# Power.net
KiCad netlist of a schematic drawn in Altium Designer
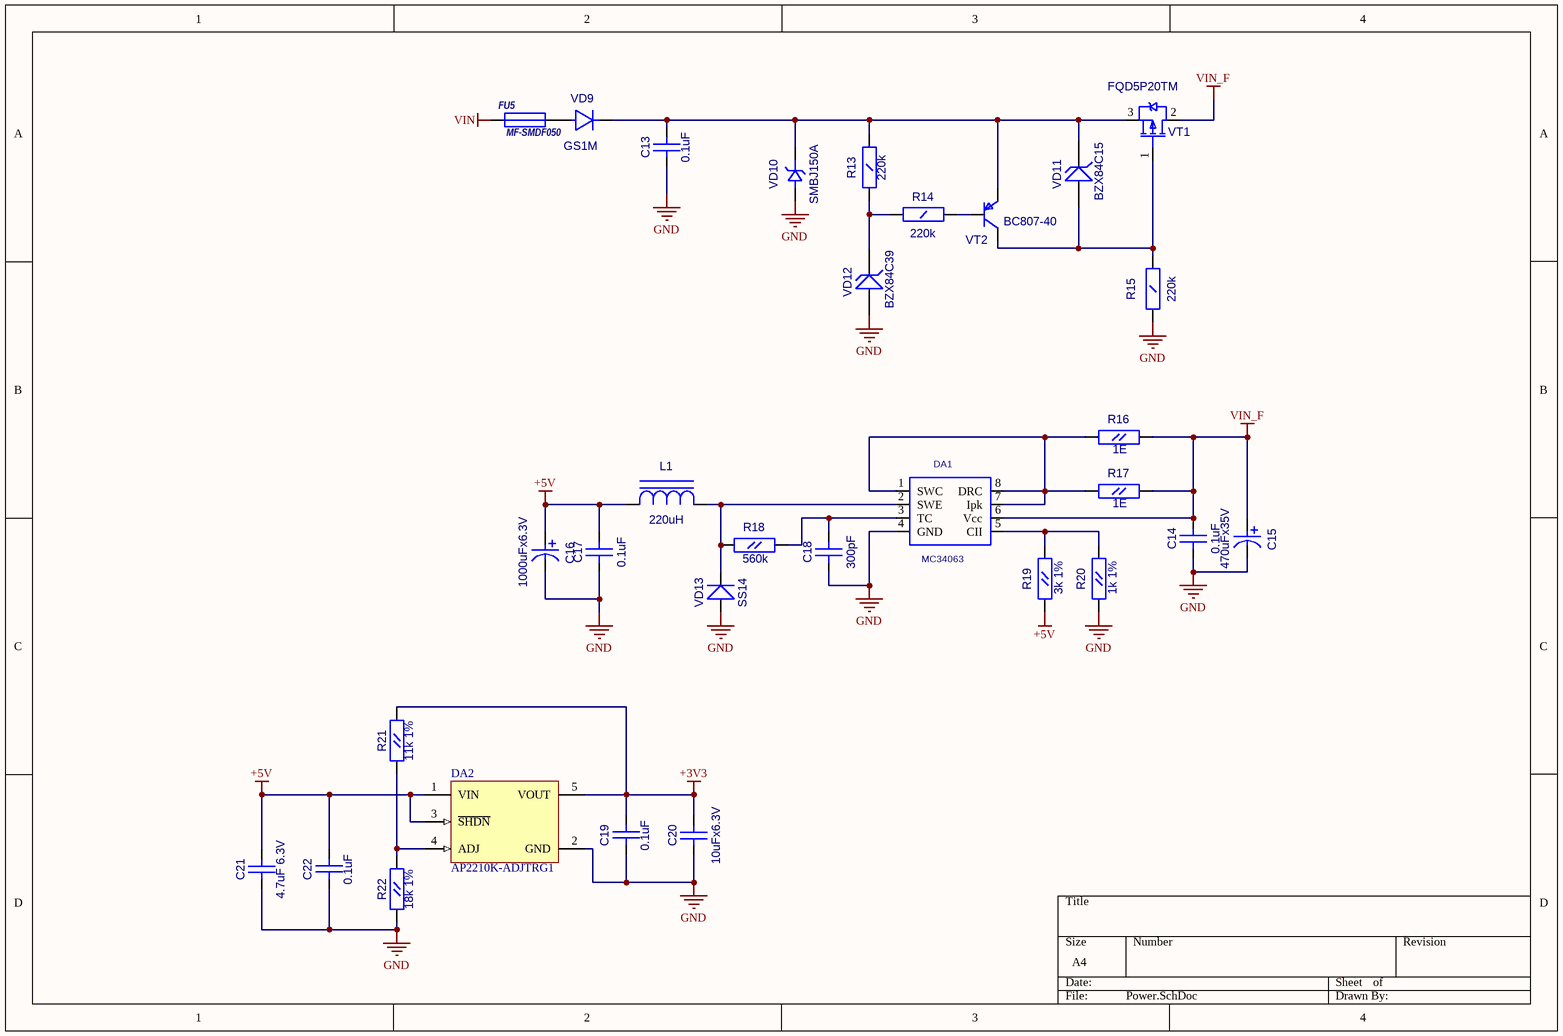
[diagram p0: Power.SchDoc]

(export (version "E")
  (design (tool "Eeschema 10.0.6"))
  (components
    (comp (ref "C13")
      (value "0.1uF")
      (footprint "CC1206")
      (description "CC1206")
      (libsource (lib "gprs_modem_2") (part "CC1206"))
    )
    (comp (ref "C14")
      (value "0.1uF")
      (footprint "CC0603")
      (description "CC0603")
      (libsource (lib "gprs_modem_2") (part "CC0603"))
    )
    (comp (ref "C15")
      (value "470uFx35V")
      (footprint "CC16X10_CAP0.5(1)(Primary)")
      (description "CAP0.5(1)")
      (libsource (lib "gprs_modem_2") (part "CAP0.5(1)"))
    )
    (comp (ref "C16")
      (value "1000uFx6.3V")
      (footprint "CC8X3.5")
      (description "CAP0.35")
      (libsource (lib "gprs_modem_2") (part "CAP0.35"))
    )
    (comp (ref "C17")
      (value "0.1uF")
      (footprint "CC0603")
      (description "CC0603")
      (libsource (lib "gprs_modem_2") (part "CC0603"))
    )
    (comp (ref "C18")
      (value "300pF")
      (footprint "CC0603")
      (description "CC0603")
      (libsource (lib "gprs_modem_2") (part "CC0603"))
    )
    (comp (ref "C19")
      (value "0.1uF")
      (footprint "CC0603")
      (description "CC0603")
      (libsource (lib "gprs_modem_2") (part "CC0603"))
    )
    (comp (ref "C20")
      (value "10uFx6.3V")
      (footprint "CC0805")
      (description "CC0805")
      (libsource (lib "gprs_modem_2") (part "CC0805"))
    )
    (comp (ref "C21")
      (value "4.7uF 6.3V")
      (footprint "CC0805")
      (description "CC0805")
      (libsource (lib "gprs_modem_2") (part "CC0805"))
    )
    (comp (ref "C22")
      (value "0.1uF")
      (footprint "CC0603")
      (description "CC0603")
      (libsource (lib "gprs_modem_2") (part "CC0603"))
    )
    (comp (ref "DA1") (value "MC34063") (footprint "SO-8") (libsource (lib "Schetchik") (part "MC34063")))
    (comp (ref "DA2")
      (value "AP2210K-ADJTRG1")
      (footprint "SOT23-5")
      (fields (field (name "PUBLISHER") "Altium Limited"))
      (libsource (lib "gprs_modem_2") (part "MCP1824T-ADJE/OT"))
    )
    (comp (ref "FU5")
      (value "MF-SMDF050")
      (footprint "MF-SMDF")
      (description "MF-SMDF")
      (libsource (lib "gprs_modem_2") (part "MF-SMDF"))
    )
    (comp (ref "L1")
      (value "220uH")
      (footprint "SDR0805")
      (description "SDR0805")
      (libsource (lib "gprs_modem_2") (part "SDR0805"))
    )
    (comp (ref "R13")
      (value "220k")
      (footprint "RC1206")
      (description "RC1206")
      (libsource (lib "gprs_modem_2") (part "RC1206"))
    )
    (comp (ref "R14")
      (value "220k")
      (footprint "RC1206")
      (description "RC1206")
      (libsource (lib "gprs_modem_2") (part "RC1206"))
    )
    (comp (ref "R15")
      (value "220k")
      (footprint "RC1206")
      (description "RC1206")
      (libsource (lib "gprs_modem_2") (part "RC1206"))
    )
    (comp (ref "R16")
      (value "1E")
      (footprint "RC0805")
      (description "RC0805")
      (libsource (lib "gprs_modem_2") (part "RC0805"))
    )
    (comp (ref "R17")
      (value "1E")
      (footprint "RC0805")
      (description "RC0805")
      (libsource (lib "gprs_modem_2") (part "RC0805"))
    )
    (comp (ref "R18")
      (value "560k")
      (footprint "RC0603")
      (description "RC0603")
      (libsource (lib "gprs_modem_2") (part "RC0603"))
    )
    (comp (ref "R19")
      (value "3k 1%")
      (footprint "RC0603")
      (description "RC0603")
      (libsource (lib "gprs_modem_2") (part "RC0603"))
    )
    (comp (ref "R20")
      (value "1k 1%")
      (footprint "RC0603")
      (description "RC0603")
      (libsource (lib "gprs_modem_2") (part "RC0603"))
    )
    (comp (ref "R21")
      (value "11k 1%")
      (footprint "RC0603")
      (description "RC0603")
      (libsource (lib "gprs_modem_2") (part "RC0603"))
    )
    (comp (ref "R22")
      (value "18k 1%")
      (footprint "RC0603")
      (description "RC0603")
      (libsource (lib "gprs_modem_2") (part "RC0603"))
    )
    (comp (ref "VD9") (value "GS1M") (footprint "SMA") (libsource (lib "gprs_modem") (part "GS1M")))
    (comp (ref "VD10")
      (value "SMBJ150A")
      (footprint "SMB")
      (description "SMBJ")
      (libsource (lib "gprs_modem_2") (part "SMBJ"))
    )
    (comp (ref "VD11")
      (value "BZX84C15")
      (footprint "SOT-23(123)")
      (description "Zener Voltage Regulator Diode")
      (libsource (lib "gprs_modem_2") (part "BZX84"))
    )
    (comp (ref "VD12")
      (value "BZX84C39")
      (footprint "SOT-23(123)")
      (description "Zener Voltage Regulator Diode")
      (libsource (lib "gprs_modem_2") (part "BZX84"))
    )
    (comp (ref "VD13")
      (value "SS14")
      (footprint "SMA")
      (description "Schottky Rectifier")
      (libsource (lib "gprs_modem_2") (part "SS14"))
    )
    (comp (ref "VT1")
      (value "FQD5P20TM")
      (footprint "D-PAK(TO-252AA)")
      (description "HEXFET Power MOSFET")
      (libsource (lib "gprs_modem_2") (part "IRFR9220"))
    )
    (comp (ref "VT2")
      (value "BC807-40")
      (footprint "SOT-23(123)")
      (description "BC857B")
      (libsource (lib "gprs_modem") (part "BC857B"))
    )
  )
  (nets
    (net (code "1") (name "+3V3") (class "Default")
      (node (ref "C19") (pin "1") (pinfunction "A_1") (pintype "passive"))
      (node (ref "C20") (pin "2") (pinfunction "B_2") (pintype "passive"))
      (node (ref "DA2") (pin "5") (pinfunction "VOUT_5") (pintype "power_in"))
      (node (ref "R21") (pin "2") (pinfunction "B_2") (pintype "passive"))
    )
    (net (code "2") (name "+5V") (class "Default")
      (node (ref "C16") (pin "1") (pintype "passive"))
      (node (ref "C17") (pin "2") (pinfunction "B_2") (pintype "passive"))
      (node (ref "C21") (pin "2") (pinfunction "B_2") (pintype "passive"))
      (node (ref "C22") (pin "1") (pinfunction "A_1") (pintype "passive"))
      (node (ref "DA2") (pin "1") (pinfunction "VIN_1") (pintype "power_in"))
      (node (ref "DA2") (pin "3") (pinfunction "~{SHDN}_3") (pintype "input"))
      (node (ref "L1") (pin "1") (pinfunction "C_1") (pintype "passive"))
      (node (ref "R19") (pin "1") (pinfunction "A_1") (pintype "passive"))
    )
    (net (code "3") (name "GND") (class "Default")
      (node (ref "C13") (pin "1") (pinfunction "A_1") (pintype "passive"))
      (node (ref "C14") (pin "1") (pinfunction "A_1") (pintype "passive"))
      (node (ref "C15") (pin "1") (pintype "passive"))
      (node (ref "C16") (pin "2") (pintype "passive"))
      (node (ref "C17") (pin "1") (pinfunction "A_1") (pintype "passive"))
      (node (ref "C18") (pin "1") (pinfunction "A_1") (pintype "passive"))
      (node (ref "C19") (pin "2") (pinfunction "B_2") (pintype "passive"))
      (node (ref "C20") (pin "1") (pinfunction "A_1") (pintype "passive"))
      (node (ref "C21") (pin "1") (pinfunction "A_1") (pintype "passive"))
      (node (ref "C22") (pin "2") (pinfunction "B_2") (pintype "passive"))
      (node (ref "DA1") (pin "4") (pinfunction "GND_4") (pintype "passive"))
      (node (ref "DA2") (pin "2") (pinfunction "GND_2") (pintype "power_in"))
      (node (ref "R15") (pin "2") (pinfunction "B_2") (pintype "passive"))
      (node (ref "R20") (pin "1") (pinfunction "A_1") (pintype "passive"))
      (node (ref "R22") (pin "1") (pinfunction "A_1") (pintype "passive"))
      (node (ref "VD10") (pin "1") (pinfunction "A_1") (pintype "passive"))
      (node (ref "VD12") (pin "1") (pinfunction "A_1") (pintype "passive"))
      (node (ref "VD13") (pin "1") (pinfunction "A_1") (pintype "passive"))
    )
    (net (code "4") (name "Net-(C13-B)") (class "Default")
      (node (ref "C13") (pin "2") (pinfunction "B_2") (pintype "passive"))
      (node (ref "R13") (pin "2") (pinfunction "B_2") (pintype "passive"))
      (node (ref "VD10") (pin "2") (pinfunction "K_2") (pintype "passive"))
      (node (ref "VD11") (pin "3") (pinfunction "K_3") (pintype "passive"))
      (node (ref "VD9") (pin "2") (pinfunction "K_2") (pintype "passive"))
      (node (ref "VT1") (pin "3") (pinfunction "S_3") (pintype "passive"))
      (node (ref "VT2") (pin "2") (pinfunction "E_2") (pintype "passive"))
    )
    (net (code "5") (name "Net-(C18-B)") (class "Default")
      (node (ref "C18") (pin "2") (pinfunction "B_2") (pintype "passive"))
      (node (ref "DA1") (pin "3") (pinfunction "TC_3") (pintype "passive"))
      (node (ref "R18") (pin "2") (pinfunction "B_2") (pintype "passive"))
    )
    (net (code "6") (name "Net-(DA1-CII)") (class "Default")
      (node (ref "DA1") (pin "5") (pinfunction "CII_5") (pintype "passive"))
      (node (ref "R19") (pin "2") (pinfunction "B_2") (pintype "passive"))
      (node (ref "R20") (pin "2") (pinfunction "B_2") (pintype "passive"))
    )
    (net (code "7") (name "Net-(DA1-DRC)") (class "Default")
      (node (ref "DA1") (pin "1") (pinfunction "SWC_1") (pintype "passive"))
      (node (ref "DA1") (pin "7") (pinfunction "Ipk_7") (pintype "passive"))
      (node (ref "DA1") (pin "8") (pinfunction "DRC_8") (pintype "passive"))
      (node (ref "R16") (pin "1") (pinfunction "A_1") (pintype "passive"))
      (node (ref "R17") (pin "1") (pinfunction "A_1") (pintype "passive"))
    )
    (net (code "8") (name "Net-(DA1-SWE)") (class "Default")
      (node (ref "DA1") (pin "2") (pinfunction "SWE_2") (pintype "passive"))
      (node (ref "L1") (pin "2") (pinfunction "A_2") (pintype "passive"))
      (node (ref "R18") (pin "1") (pinfunction "A_1") (pintype "passive"))
      (node (ref "VD13") (pin "2") (pinfunction "K_2") (pintype "passive"))
    )
    (net (code "9") (name "Net-(DA2-ADJ)") (class "Default")
      (node (ref "DA2") (pin "4") (pinfunction "ADJ_4") (pintype "input"))
      (node (ref "R21") (pin "1") (pinfunction "A_1") (pintype "passive"))
      (node (ref "R22") (pin "2") (pinfunction "B_2") (pintype "passive"))
    )
    (net (code "10") (name "Net-(R13-A)") (class "Default")
      (node (ref "R13") (pin "1") (pinfunction "A_1") (pintype "passive"))
      (node (ref "R14") (pin "1") (pinfunction "A_1") (pintype "passive"))
      (node (ref "VD12") (pin "3") (pinfunction "K_3") (pintype "passive"))
    )
    (net (code "11") (name "Net-(R14-B)") (class "Default")
      (node (ref "R14") (pin "2") (pinfunction "B_2") (pintype "passive"))
      (node (ref "VT2") (pin "1") (pinfunction "B_1") (pintype "passive"))
    )
    (net (code "12") (name "Net-(R15-A)") (class "Default")
      (node (ref "R15") (pin "1") (pinfunction "A_1") (pintype "passive"))
      (node (ref "VD11") (pin "1") (pinfunction "A_1") (pintype "passive"))
      (node (ref "VT1") (pin "1") (pinfunction "G_1") (pintype "passive"))
      (node (ref "VT2") (pin "3") (pinfunction "C_3") (pintype "passive"))
    )
    (net (code "13") (name "Net-(VD9-A)") (class "Default")
      (node (ref "FU5") (pin "2") (pintype "passive"))
      (node (ref "VD9") (pin "1") (pinfunction "A_1") (pintype "passive"))
    )
    (net (code "14") (name "VIN") (class "Default") (node (ref "FU5") (pin "1") (pintype "passive")))
    (net (code "15") (name "VIN_F") (class "Default")
      (node (ref "C14") (pin "2") (pinfunction "B_2") (pintype "passive"))
      (node (ref "C15") (pin "2") (pintype "passive"))
      (node (ref "DA1") (pin "6") (pinfunction "Vcc_6") (pintype "passive"))
      (node (ref "R16") (pin "2") (pinfunction "B_2") (pintype "passive"))
      (node (ref "R17") (pin "2") (pinfunction "B_2") (pintype "passive"))
      (node (ref "VT1") (pin "2") (pinfunction "D_2") (pintype "passive"))
    )
  )
)
